# DD2088PoE_Daisy_Chain_CAM.net
KiCad netlist of a schematic drawn in Altium Designer
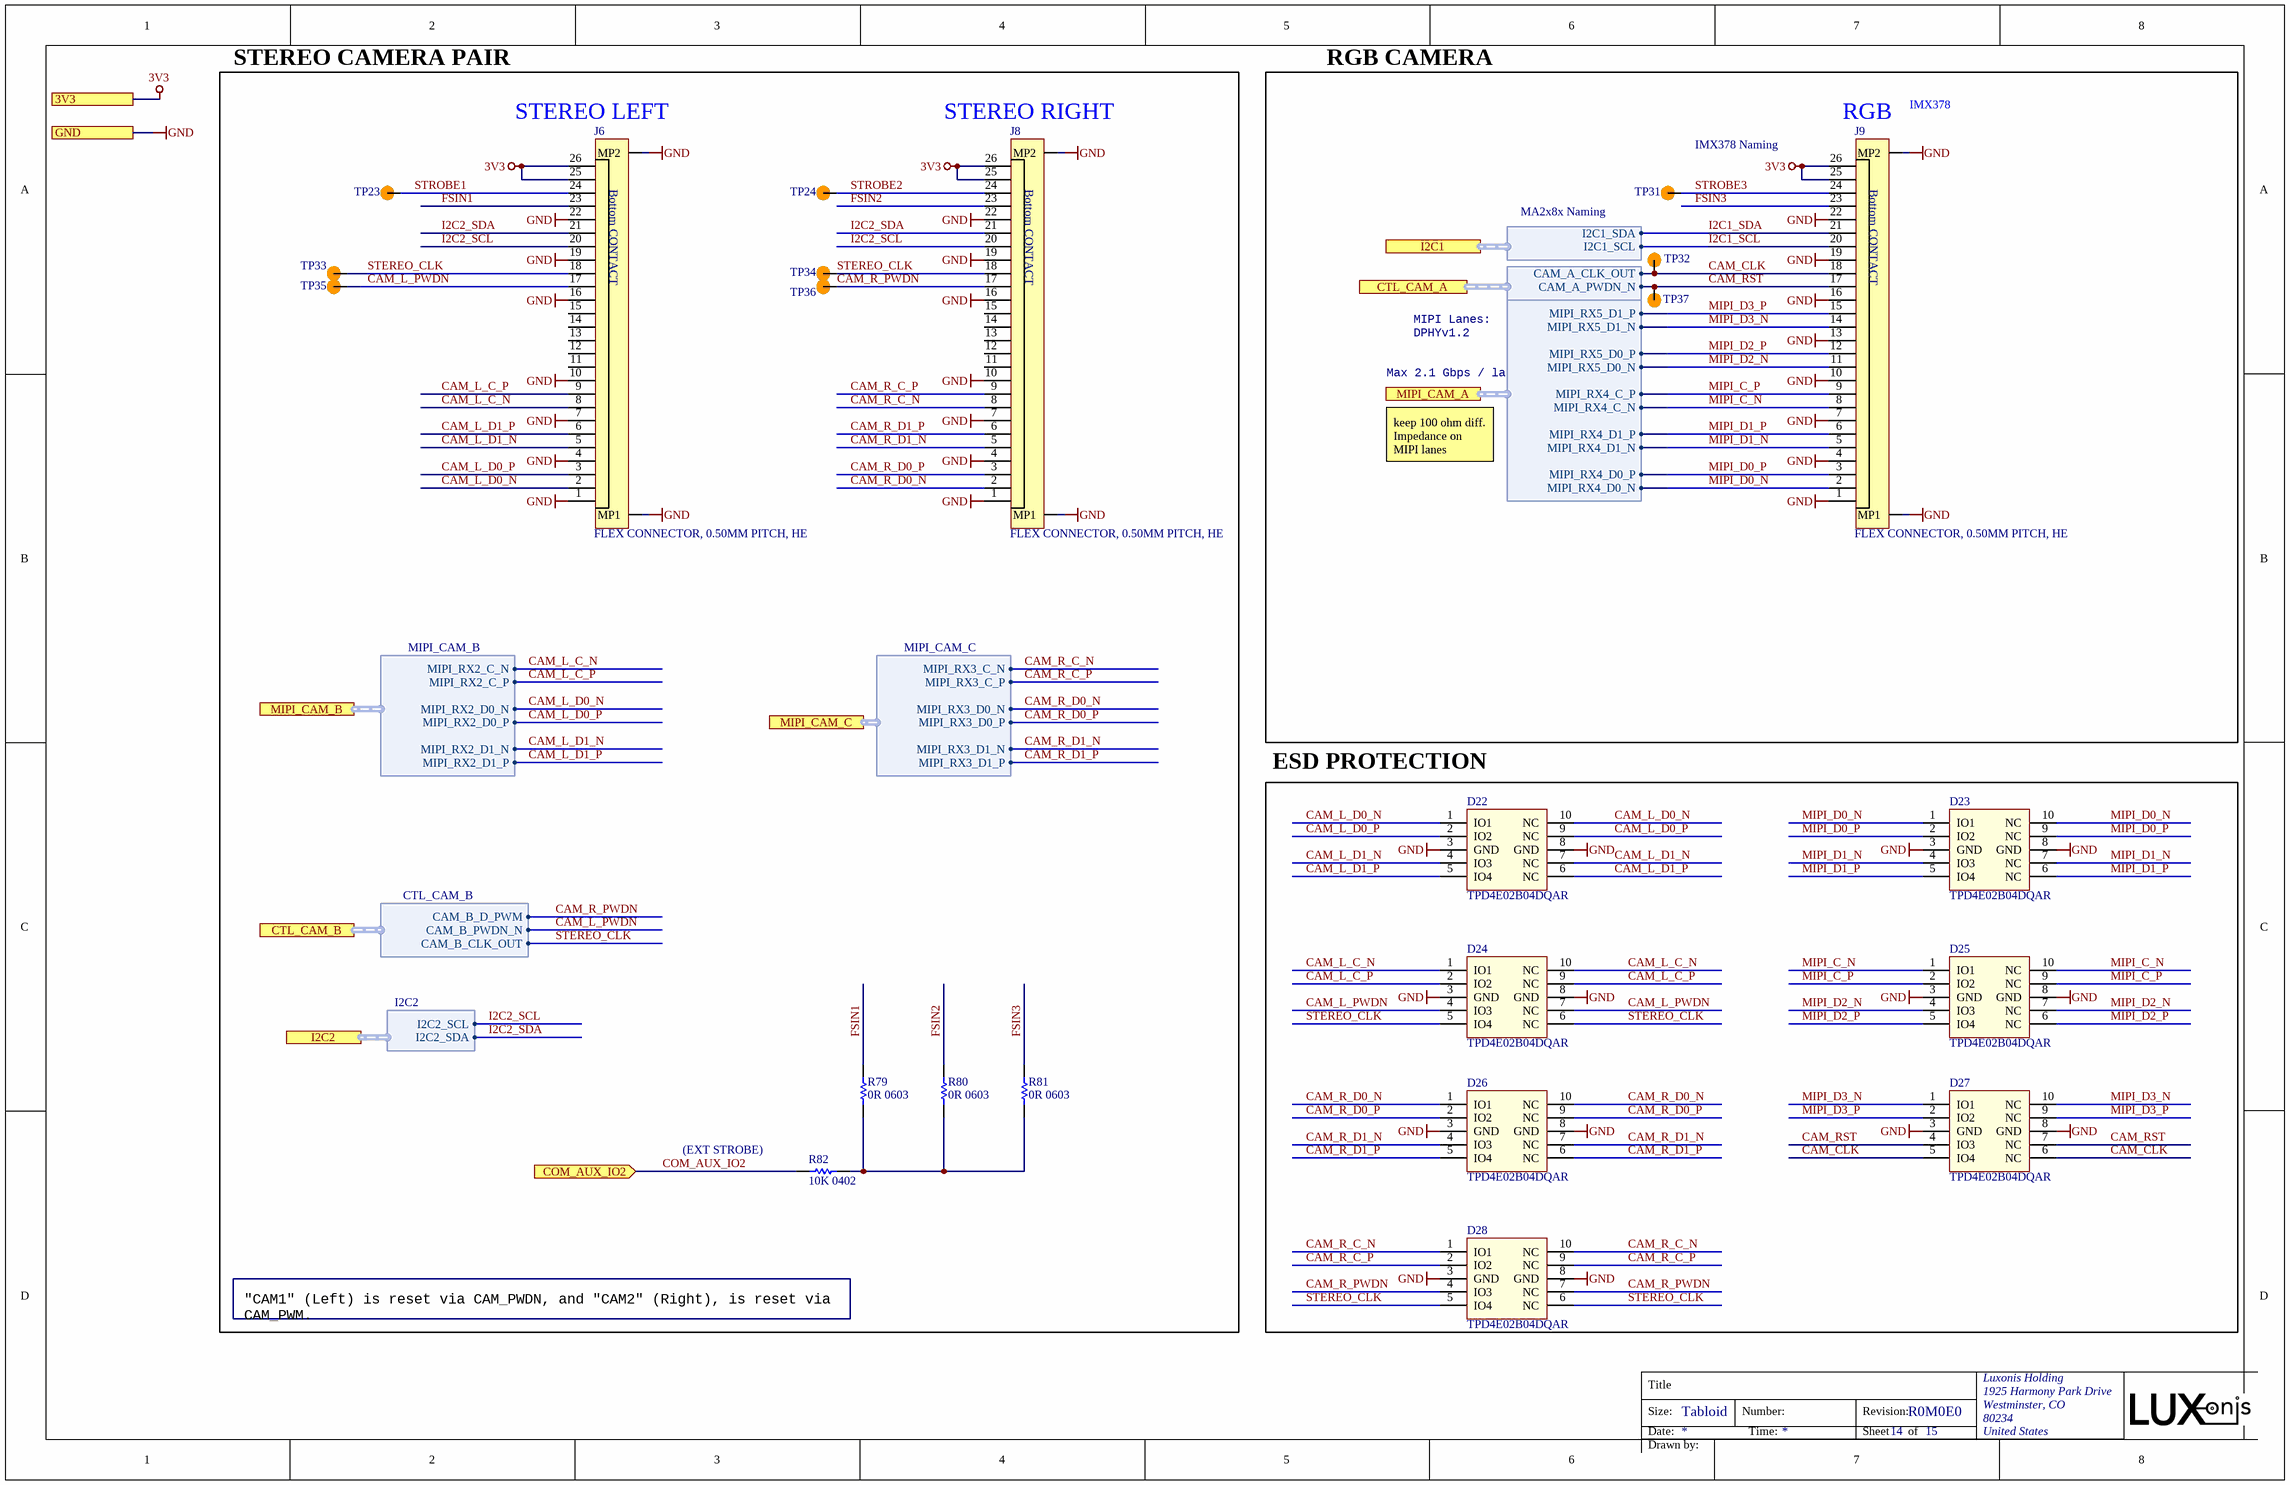
[diagram p0: DD2088PoE_Daisy_Chain_CAM.SchDoc]

(export (version "E")
  (design (tool "Eeschema 10.0.6"))
  (components
    (comp (ref "D22")
      (value "TPD4E02B04DQAR")
      (footprint "TPD4E02B04DQAR")
      (libsource (lib "LuxonisMaster") (part "TPD4E02B04DQAR"))
    )
    (comp (ref "D23")
      (value "TPD4E02B04DQAR")
      (footprint "TPD4E02B04DQAR")
      (libsource (lib "LuxonisMaster") (part "TPD4E02B04DQAR"))
    )
    (comp (ref "D24")
      (value "TPD4E02B04DQAR")
      (footprint "TPD4E02B04DQAR")
      (libsource (lib "LuxonisMaster") (part "TPD4E02B04DQAR"))
    )
    (comp (ref "D25")
      (value "TPD4E02B04DQAR")
      (footprint "TPD4E02B04DQAR")
      (libsource (lib "LuxonisMaster") (part "TPD4E02B04DQAR"))
    )
    (comp (ref "D26")
      (value "TPD4E02B04DQAR")
      (footprint "TPD4E02B04DQAR")
      (libsource (lib "LuxonisMaster") (part "TPD4E02B04DQAR"))
    )
    (comp (ref "D27")
      (value "TPD4E02B04DQAR")
      (footprint "TPD4E02B04DQAR")
      (libsource (lib "LuxonisMaster") (part "TPD4E02B04DQAR"))
    )
    (comp (ref "D28")
      (value "TPD4E02B04DQAR")
      (footprint "TPD4E02B04DQAR")
      (libsource (lib "LuxonisMaster") (part "TPD4E02B04DQAR"))
    )
    (comp (ref "J6")
      (value "FLEX CONNECTOR, 0.50MM PITCH, HE")
      (footprint "DM1090FFC:F32R-1A7H1-11026")
      (description "26 Position FFC, FPC Connector Contacts, Bottom 0.020\" (0.50mm) Surface Mount, Right Angle")
      (libsource (lib "DM1090FFC") (part "F32R-1A7H1-11026"))
    )
    (comp (ref "J8")
      (value "FLEX CONNECTOR, 0.50MM PITCH, HE")
      (footprint "DM1090FFC:F32R-1A7H1-11026")
      (description "26 Position FFC, FPC Connector Contacts, Bottom 0.020\" (0.50mm) Surface Mount, Right Angle")
      (libsource (lib "DM1090FFC") (part "F32R-1A7H1-11026"))
    )
    (comp (ref "J9")
      (value "FLEX CONNECTOR, 0.50MM PITCH, HE")
      (footprint "DM1090FFC:F32R-1A7H1-11026")
      (description "26 Position FFC, FPC Connector Contacts, Bottom 0.020\" (0.50mm) Surface Mount, Right Angle")
      (libsource (lib "DM1090FFC") (part "F32R-1A7H1-11026"))
    )
    (comp (ref "R79")
      (value "0R 0603")
      (footprint "RESC0603(1608)_N")
      (fields (field (name "TOLERANCE") "5%"))
      (libsource (lib "LuxonisMaster") (part "CRCW06030000Z0EA"))
    )
    (comp (ref "R80")
      (value "0R 0603")
      (footprint "RESC0603(1608)_N")
      (fields (field (name "TOLERANCE") "5%"))
      (libsource (lib "LuxonisMaster") (part "CRCW06030000Z0EA"))
    )
    (comp (ref "R81")
      (value "0R 0603")
      (footprint "RESC0603(1608)_N")
      (fields (field (name "TOLERANCE") "5%"))
      (libsource (lib "LuxonisMaster") (part "CRCW06030000Z0EA"))
    )
    (comp (ref "R82")
      (value "10K 0402")
      (footprint "RESC0402(1005)_N")
      (fields (field (name "TOLERANCE") "1%"))
      (libsource (lib "LuxonisMaster") (part "RC0402FR-1310KL"))
    )
    (comp (ref "TP23")
      (value "TP100_200_NS")
      (footprint "TP100_200_NS")
      (libsource (lib "LuxonisMaster") (part "TEST_POINT"))
    )
    (comp (ref "TP24")
      (value "TP100_200_NS")
      (footprint "TP100_200_NS")
      (libsource (lib "LuxonisMaster") (part "TEST_POINT"))
    )
    (comp (ref "TP31")
      (value "TP100_200_NS")
      (footprint "TP100_200_NS")
      (libsource (lib "LuxonisMaster") (part "TEST_POINT"))
    )
    (comp (ref "TP32")
      (value "TP100_200_NS")
      (footprint "TP100_200_NS")
      (libsource (lib "LuxonisMaster") (part "TEST_POINT"))
    )
    (comp (ref "TP33")
      (value "TP100_200_NS")
      (footprint "TP100_200_NS")
      (libsource (lib "LuxonisMaster") (part "TEST_POINT"))
    )
    (comp (ref "TP34")
      (value "TP100_200_NS")
      (footprint "TP100_200_NS")
      (libsource (lib "LuxonisMaster") (part "TEST_POINT"))
    )
    (comp (ref "TP35")
      (value "TP100_200_NS")
      (footprint "TP100_200_NS")
      (libsource (lib "LuxonisMaster") (part "TEST_POINT"))
    )
    (comp (ref "TP36")
      (value "TP100_200_NS")
      (footprint "TP100_200_NS")
      (libsource (lib "LuxonisMaster") (part "TEST_POINT"))
    )
    (comp (ref "TP37")
      (value "TP100_200_NS")
      (footprint "TP100_200_NS")
      (libsource (lib "LuxonisMaster") (part "TEST_POINT"))
    )
  )
  (nets
    (net (code "8") (name "/CAM_CLK") (class "Default")
      (node (ref "D27") (pin "5") (pinfunction "IO4_5") (pintype "passive"))
      (node (ref "D27") (pin "6") (pinfunction "NC_6") (pintype "passive"))
      (node (ref "J9") (pin "18") (pinfunction "18_18") (pintype "passive"))
      (node (ref "TP32") (pin "1") (pintype "passive"))
    )
    (net (code "9") (name "/CAM_L_C_N") (class "Default")
      (node (ref "D24") (pin "1") (pinfunction "IO1_1") (pintype "passive"))
      (node (ref "D24") (pin "10") (pinfunction "NC_10") (pintype "passive"))
      (node (ref "J6") (pin "8") (pinfunction "8_8") (pintype "passive"))
    )
    (net (code "10") (name "/CAM_L_C_P") (class "Default")
      (node (ref "D24") (pin "2") (pinfunction "IO2_2") (pintype "passive"))
      (node (ref "D24") (pin "9") (pinfunction "NC_9") (pintype "passive"))
      (node (ref "J6") (pin "9") (pinfunction "9_9") (pintype "passive"))
    )
    (net (code "11") (name "/CAM_L_D0_N") (class "Default")
      (node (ref "D22") (pin "1") (pinfunction "IO1_1") (pintype "passive"))
      (node (ref "D22") (pin "10") (pinfunction "NC_10") (pintype "passive"))
      (node (ref "J6") (pin "2") (pinfunction "2_2") (pintype "passive"))
    )
    (net (code "12") (name "/CAM_L_D0_P") (class "Default")
      (node (ref "D22") (pin "2") (pinfunction "IO2_2") (pintype "passive"))
      (node (ref "D22") (pin "9") (pinfunction "NC_9") (pintype "passive"))
      (node (ref "J6") (pin "3") (pinfunction "3_3") (pintype "passive"))
    )
    (net (code "13") (name "/CAM_L_D1_N") (class "Default")
      (node (ref "D22") (pin "4") (pinfunction "IO3_4") (pintype "passive"))
      (node (ref "D22") (pin "7") (pinfunction "NC_7") (pintype "passive"))
      (node (ref "J6") (pin "5") (pinfunction "5_5") (pintype "passive"))
    )
    (net (code "14") (name "/CAM_L_D1_P") (class "Default")
      (node (ref "D22") (pin "5") (pinfunction "IO4_5") (pintype "passive"))
      (node (ref "D22") (pin "6") (pinfunction "NC_6") (pintype "passive"))
      (node (ref "J6") (pin "6") (pinfunction "6_6") (pintype "passive"))
    )
    (net (code "15") (name "/CAM_L_PWDN") (class "Default")
      (node (ref "D24") (pin "4") (pinfunction "IO3_4") (pintype "passive"))
      (node (ref "D24") (pin "7") (pinfunction "NC_7") (pintype "passive"))
      (node (ref "J6") (pin "17") (pinfunction "17_17") (pintype "passive"))
      (node (ref "TP35") (pin "1") (pintype "passive"))
    )
    (net (code "16") (name "/CAM_RST") (class "Default")
      (node (ref "D27") (pin "4") (pinfunction "IO3_4") (pintype "passive"))
      (node (ref "D27") (pin "7") (pinfunction "NC_7") (pintype "passive"))
      (node (ref "J9") (pin "17") (pinfunction "17_17") (pintype "passive"))
      (node (ref "TP37") (pin "1") (pintype "passive"))
    )
    (net (code "17") (name "/CAM_R_C_N") (class "Default")
      (node (ref "D28") (pin "1") (pinfunction "IO1_1") (pintype "passive"))
      (node (ref "D28") (pin "10") (pinfunction "NC_10") (pintype "passive"))
      (node (ref "J8") (pin "8") (pinfunction "8_8") (pintype "passive"))
    )
    (net (code "18") (name "/CAM_R_C_P") (class "Default")
      (node (ref "D28") (pin "2") (pinfunction "IO2_2") (pintype "passive"))
      (node (ref "D28") (pin "9") (pinfunction "NC_9") (pintype "passive"))
      (node (ref "J8") (pin "9") (pinfunction "9_9") (pintype "passive"))
    )
    (net (code "19") (name "/CAM_R_D0_N") (class "Default")
      (node (ref "D26") (pin "1") (pinfunction "IO1_1") (pintype "passive"))
      (node (ref "D26") (pin "10") (pinfunction "NC_10") (pintype "passive"))
      (node (ref "J8") (pin "2") (pinfunction "2_2") (pintype "passive"))
    )
    (net (code "20") (name "/CAM_R_D0_P") (class "Default")
      (node (ref "D26") (pin "2") (pinfunction "IO2_2") (pintype "passive"))
      (node (ref "D26") (pin "9") (pinfunction "NC_9") (pintype "passive"))
      (node (ref "J8") (pin "3") (pinfunction "3_3") (pintype "passive"))
    )
    (net (code "21") (name "/CAM_R_D1_N") (class "Default")
      (node (ref "D26") (pin "4") (pinfunction "IO3_4") (pintype "passive"))
      (node (ref "D26") (pin "7") (pinfunction "NC_7") (pintype "passive"))
      (node (ref "J8") (pin "5") (pinfunction "5_5") (pintype "passive"))
    )
    (net (code "22") (name "/CAM_R_D1_P") (class "Default")
      (node (ref "D26") (pin "5") (pinfunction "IO4_5") (pintype "passive"))
      (node (ref "D26") (pin "6") (pinfunction "NC_6") (pintype "passive"))
      (node (ref "J8") (pin "6") (pinfunction "6_6") (pintype "passive"))
    )
    (net (code "23") (name "/CAM_R_PWDN") (class "Default")
      (node (ref "D28") (pin "4") (pinfunction "IO3_4") (pintype "passive"))
      (node (ref "D28") (pin "7") (pinfunction "NC_7") (pintype "passive"))
      (node (ref "J8") (pin "17") (pinfunction "17_17") (pintype "passive"))
      (node (ref "TP36") (pin "1") (pintype "passive"))
    )
    (net (code "24") (name "/COM_AUX_IO2") (class "Default")
      (node (ref "R82") (pin "1") (pinfunction "1_1") (pintype "passive"))
    )
    (net (code "26") (name "/FSIN1") (class "Default")
      (node (ref "J6") (pin "23") (pinfunction "23_23") (pintype "passive"))
      (node (ref "R79") (pin "2") (pinfunction "2_2") (pintype "passive"))
    )
    (net (code "27") (name "/FSIN2") (class "Default")
      (node (ref "J8") (pin "23") (pinfunction "23_23") (pintype "passive"))
      (node (ref "R80") (pin "2") (pinfunction "2_2") (pintype "passive"))
    )
    (net (code "28") (name "/FSIN3") (class "Default")
      (node (ref "J9") (pin "23") (pinfunction "23_23") (pintype "passive"))
      (node (ref "R81") (pin "2") (pinfunction "2_2") (pintype "passive"))
    )
    (net (code "29") (name "/I2C1_SCL") (class "Default")
      (node (ref "J9") (pin "20") (pinfunction "20_20") (pintype "passive"))
    )
    (net (code "30") (name "/I2C1_SDA") (class "Default")
      (node (ref "J9") (pin "21") (pinfunction "21_21") (pintype "passive"))
    )
    (net (code "31") (name "/I2C2_SCL") (class "Default")
      (node (ref "J6") (pin "20") (pinfunction "20_20") (pintype "passive"))
      (node (ref "J8") (pin "20") (pinfunction "20_20") (pintype "passive"))
    )
    (net (code "32") (name "/I2C2_SDA") (class "Default")
      (node (ref "J6") (pin "21") (pinfunction "21_21") (pintype "passive"))
      (node (ref "J8") (pin "21") (pinfunction "21_21") (pintype "passive"))
    )
    (net (code "33") (name "/MIPI_C_N") (class "Default")
      (node (ref "D25") (pin "1") (pinfunction "IO1_1") (pintype "passive"))
      (node (ref "D25") (pin "10") (pinfunction "NC_10") (pintype "passive"))
      (node (ref "J9") (pin "8") (pinfunction "8_8") (pintype "passive"))
    )
    (net (code "34") (name "/MIPI_C_P") (class "Default")
      (node (ref "D25") (pin "2") (pinfunction "IO2_2") (pintype "passive"))
      (node (ref "D25") (pin "9") (pinfunction "NC_9") (pintype "passive"))
      (node (ref "J9") (pin "9") (pinfunction "9_9") (pintype "passive"))
    )
    (net (code "35") (name "/MIPI_D0_N") (class "Default")
      (node (ref "D23") (pin "1") (pinfunction "IO1_1") (pintype "passive"))
      (node (ref "D23") (pin "10") (pinfunction "NC_10") (pintype "passive"))
      (node (ref "J9") (pin "2") (pinfunction "2_2") (pintype "passive"))
    )
    (net (code "36") (name "/MIPI_D0_P") (class "Default")
      (node (ref "D23") (pin "2") (pinfunction "IO2_2") (pintype "passive"))
      (node (ref "D23") (pin "9") (pinfunction "NC_9") (pintype "passive"))
      (node (ref "J9") (pin "3") (pinfunction "3_3") (pintype "passive"))
    )
    (net (code "37") (name "/MIPI_D1_N") (class "Default")
      (node (ref "D23") (pin "4") (pinfunction "IO3_4") (pintype "passive"))
      (node (ref "D23") (pin "7") (pinfunction "NC_7") (pintype "passive"))
      (node (ref "J9") (pin "5") (pinfunction "5_5") (pintype "passive"))
    )
    (net (code "38") (name "/MIPI_D1_P") (class "Default")
      (node (ref "D23") (pin "5") (pinfunction "IO4_5") (pintype "passive"))
      (node (ref "D23") (pin "6") (pinfunction "NC_6") (pintype "passive"))
      (node (ref "J9") (pin "6") (pinfunction "6_6") (pintype "passive"))
    )
    (net (code "39") (name "/MIPI_D2_N") (class "Default")
      (node (ref "D25") (pin "4") (pinfunction "IO3_4") (pintype "passive"))
      (node (ref "D25") (pin "7") (pinfunction "NC_7") (pintype "passive"))
      (node (ref "J9") (pin "11") (pinfunction "11_11") (pintype "passive"))
    )
    (net (code "40") (name "/MIPI_D2_P") (class "Default")
      (node (ref "D25") (pin "5") (pinfunction "IO4_5") (pintype "passive"))
      (node (ref "D25") (pin "6") (pinfunction "NC_6") (pintype "passive"))
      (node (ref "J9") (pin "12") (pinfunction "12_12") (pintype "passive"))
    )
    (net (code "41") (name "/MIPI_D3_N") (class "Default")
      (node (ref "D27") (pin "1") (pinfunction "IO1_1") (pintype "passive"))
      (node (ref "D27") (pin "10") (pinfunction "NC_10") (pintype "passive"))
      (node (ref "J9") (pin "14") (pinfunction "14_14") (pintype "passive"))
    )
    (net (code "42") (name "/MIPI_D3_P") (class "Default")
      (node (ref "D27") (pin "2") (pinfunction "IO2_2") (pintype "passive"))
      (node (ref "D27") (pin "9") (pinfunction "NC_9") (pintype "passive"))
      (node (ref "J9") (pin "15") (pinfunction "15_15") (pintype "passive"))
    )
    (net (code "43") (name "/STEREO_CLK") (class "Default")
      (node (ref "D24") (pin "5") (pinfunction "IO4_5") (pintype "passive"))
      (node (ref "D24") (pin "6") (pinfunction "NC_6") (pintype "passive"))
      (node (ref "D28") (pin "5") (pinfunction "IO4_5") (pintype "passive"))
      (node (ref "D28") (pin "6") (pinfunction "NC_6") (pintype "passive"))
      (node (ref "J6") (pin "18") (pinfunction "18_18") (pintype "passive"))
      (node (ref "J8") (pin "18") (pinfunction "18_18") (pintype "passive"))
      (node (ref "TP33") (pin "1") (pintype "passive"))
      (node (ref "TP34") (pin "1") (pintype "passive"))
    )
    (net (code "44") (name "/STROBE1") (class "Default")
      (node (ref "J6") (pin "24") (pinfunction "24_24") (pintype "passive"))
      (node (ref "TP23") (pin "1") (pintype "passive"))
    )
    (net (code "45") (name "/STROBE2") (class "Default")
      (node (ref "J8") (pin "24") (pinfunction "24_24") (pintype "passive"))
      (node (ref "TP24") (pin "1") (pintype "passive"))
    )
    (net (code "46") (name "/STROBE3") (class "Default")
      (node (ref "J9") (pin "24") (pinfunction "24_24") (pintype "passive"))
      (node (ref "TP31") (pin "1") (pintype "passive"))
    )
    (net (code "53") (name "3V3") (class "Default")
      (node (ref "J6") (pin "25") (pinfunction "25_25") (pintype "passive"))
      (node (ref "J6") (pin "26") (pinfunction "26_26") (pintype "passive"))
      (node (ref "J8") (pin "25") (pinfunction "25_25") (pintype "passive"))
      (node (ref "J8") (pin "26") (pinfunction "26_26") (pintype "passive"))
      (node (ref "J9") (pin "25") (pinfunction "25_25") (pintype "passive"))
      (node (ref "J9") (pin "26") (pinfunction "26_26") (pintype "passive"))
    )
    (net (code "54") (name "GND") (class "Default")
      (node (ref "D22") (pin "3") (pinfunction "GND_3") (pintype "passive"))
      (node (ref "D22") (pin "8") (pinfunction "GND_8") (pintype "passive"))
      (node (ref "D23") (pin "3") (pinfunction "GND_3") (pintype "passive"))
      (node (ref "D23") (pin "8") (pinfunction "GND_8") (pintype "passive"))
      (node (ref "D24") (pin "3") (pinfunction "GND_3") (pintype "passive"))
      (node (ref "D24") (pin "8") (pinfunction "GND_8") (pintype "passive"))
      (node (ref "D25") (pin "3") (pinfunction "GND_3") (pintype "passive"))
      (node (ref "D25") (pin "8") (pinfunction "GND_8") (pintype "passive"))
      (node (ref "D26") (pin "3") (pinfunction "GND_3") (pintype "passive"))
      (node (ref "D26") (pin "8") (pinfunction "GND_8") (pintype "passive"))
      (node (ref "D27") (pin "3") (pinfunction "GND_3") (pintype "passive"))
      (node (ref "D27") (pin "8") (pinfunction "GND_8") (pintype "passive"))
      (node (ref "D28") (pin "3") (pinfunction "GND_3") (pintype "passive"))
      (node (ref "D28") (pin "8") (pinfunction "GND_8") (pintype "passive"))
      (node (ref "J6") (pin "1") (pinfunction "1_1") (pintype "passive"))
      (node (ref "J6") (pin "10") (pinfunction "10_10") (pintype "passive"))
      (node (ref "J6") (pin "16") (pinfunction "16_16") (pintype "passive"))
      (node (ref "J6") (pin "19") (pinfunction "19_19") (pintype "passive"))
      (node (ref "J6") (pin "22") (pinfunction "22_22") (pintype "passive"))
      (node (ref "J6") (pin "4") (pinfunction "4_4") (pintype "passive"))
      (node (ref "J6") (pin "7") (pinfunction "7_7") (pintype "passive"))
      (node (ref "J6") (pin "MP1") (pinfunction "MP1_MP1") (pintype "passive"))
      (node (ref "J6") (pin "MP2") (pinfunction "MP2_MP2") (pintype "passive"))
      (node (ref "J8") (pin "1") (pinfunction "1_1") (pintype "passive"))
      (node (ref "J8") (pin "10") (pinfunction "10_10") (pintype "passive"))
      (node (ref "J8") (pin "16") (pinfunction "16_16") (pintype "passive"))
      (node (ref "J8") (pin "19") (pinfunction "19_19") (pintype "passive"))
      (node (ref "J8") (pin "22") (pinfunction "22_22") (pintype "passive"))
      (node (ref "J8") (pin "4") (pinfunction "4_4") (pintype "passive"))
      (node (ref "J8") (pin "7") (pinfunction "7_7") (pintype "passive"))
      (node (ref "J8") (pin "MP1") (pinfunction "MP1_MP1") (pintype "passive"))
      (node (ref "J8") (pin "MP2") (pinfunction "MP2_MP2") (pintype "passive"))
      (node (ref "J9") (pin "1") (pinfunction "1_1") (pintype "passive"))
      (node (ref "J9") (pin "10") (pinfunction "10_10") (pintype "passive"))
      (node (ref "J9") (pin "13") (pinfunction "13_13") (pintype "passive"))
      (node (ref "J9") (pin "16") (pinfunction "16_16") (pintype "passive"))
      (node (ref "J9") (pin "19") (pinfunction "19_19") (pintype "passive"))
      (node (ref "J9") (pin "22") (pinfunction "22_22") (pintype "passive"))
      (node (ref "J9") (pin "4") (pinfunction "4_4") (pintype "passive"))
      (node (ref "J9") (pin "7") (pinfunction "7_7") (pintype "passive"))
      (node (ref "J9") (pin "MP1") (pinfunction "MP1_MP1") (pintype "passive"))
      (node (ref "J9") (pin "MP2") (pinfunction "MP2_MP2") (pintype "passive"))
    )
    (net (code "55") (name "Net-(R79-Pad1)") (class "Default")
      (node (ref "R79") (pin "1") (pinfunction "1_1") (pintype "passive"))
      (node (ref "R80") (pin "1") (pinfunction "1_1") (pintype "passive"))
      (node (ref "R81") (pin "1") (pinfunction "1_1") (pintype "passive"))
      (node (ref "R82") (pin "2") (pinfunction "2_2") (pintype "passive"))
    )
    (net (code "56") (name "unconnected-(J6-Pad11)") (class "Default")
      (node (ref "J6") (pin "11") (pinfunction "11_11") (pintype "passive"))
    )
    (net (code "57") (name "unconnected-(J6-Pad12)") (class "Default")
      (node (ref "J6") (pin "12") (pinfunction "12_12") (pintype "passive"))
    )
    (net (code "58") (name "unconnected-(J6-Pad13)") (class "Default")
      (node (ref "J6") (pin "13") (pinfunction "13_13") (pintype "passive"))
    )
    (net (code "59") (name "unconnected-(J6-Pad14)") (class "Default")
      (node (ref "J6") (pin "14") (pinfunction "14_14") (pintype "passive"))
    )
    (net (code "60") (name "unconnected-(J6-Pad15)") (class "Default")
      (node (ref "J6") (pin "15") (pinfunction "15_15") (pintype "passive"))
    )
    (net (code "61") (name "unconnected-(J8-Pad11)") (class "Default")
      (node (ref "J8") (pin "11") (pinfunction "11_11") (pintype "passive"))
    )
    (net (code "62") (name "unconnected-(J8-Pad12)") (class "Default")
      (node (ref "J8") (pin "12") (pinfunction "12_12") (pintype "passive"))
    )
    (net (code "63") (name "unconnected-(J8-Pad13)") (class "Default")
      (node (ref "J8") (pin "13") (pinfunction "13_13") (pintype "passive"))
    )
    (net (code "64") (name "unconnected-(J8-Pad14)") (class "Default")
      (node (ref "J8") (pin "14") (pinfunction "14_14") (pintype "passive"))
    )
    (net (code "65") (name "unconnected-(J8-Pad15)") (class "Default")
      (node (ref "J8") (pin "15") (pinfunction "15_15") (pintype "passive"))
    )
  )
)
